# pm-batt-ti.net
KiCad netlist of a schematic drawn in EAGLE
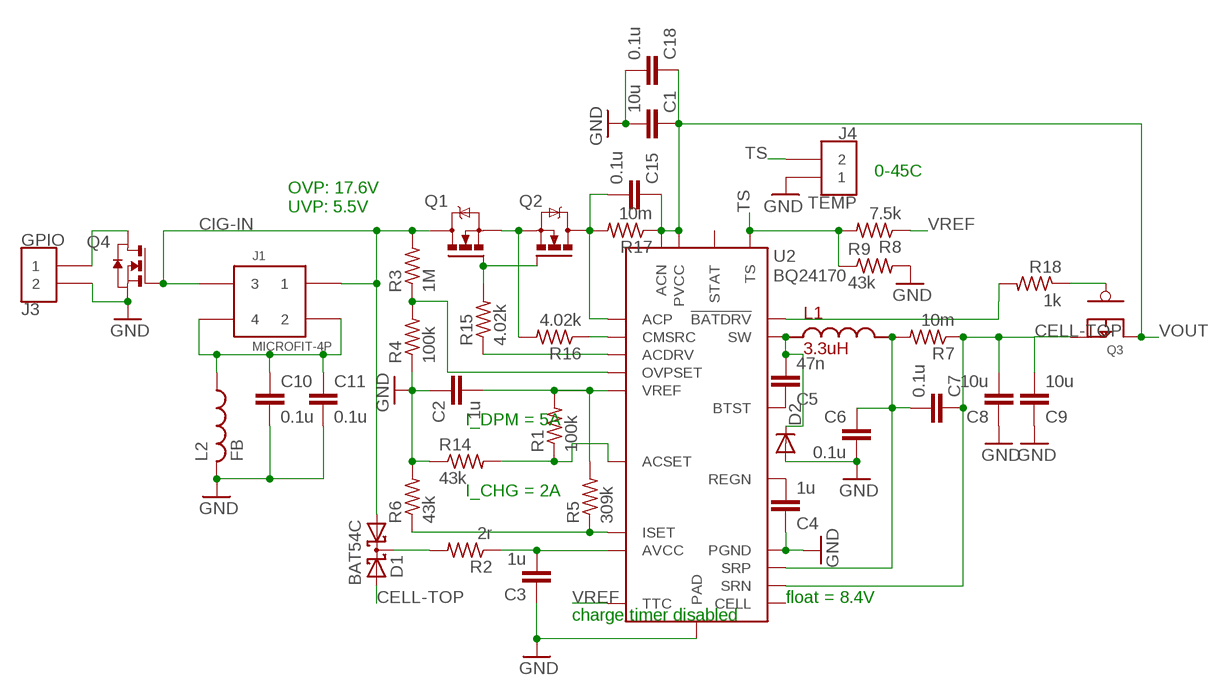
[diagram p0: schematic, sheet 1]
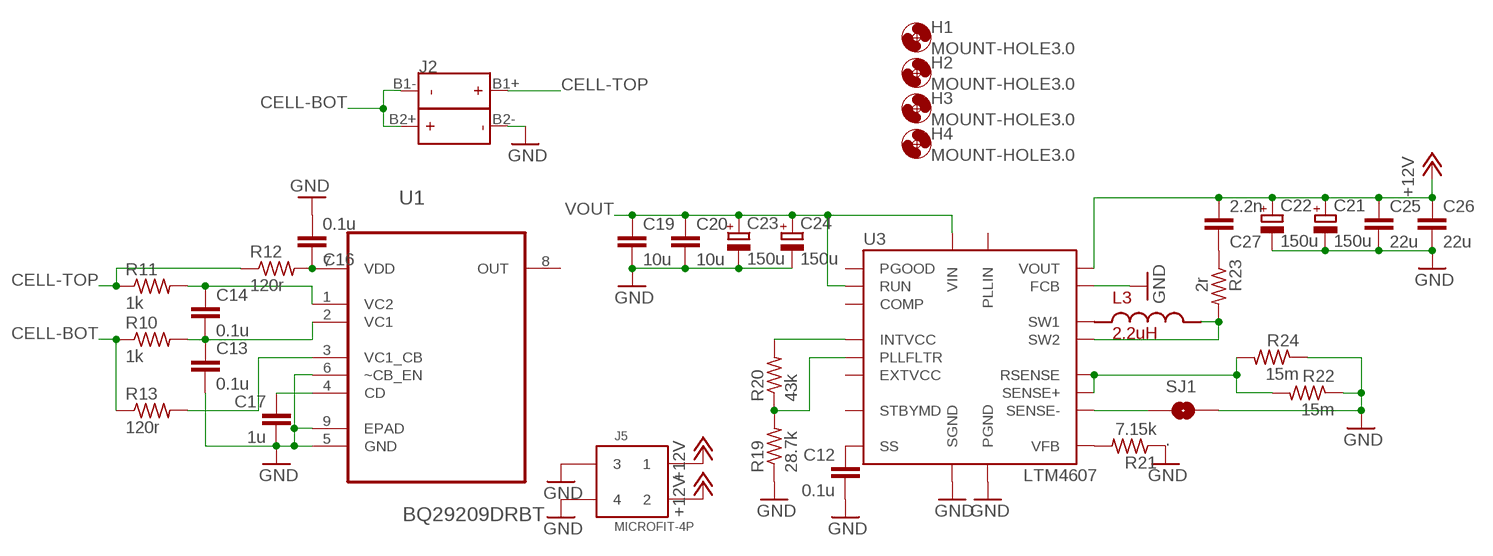
[diagram p1: schematic, sheet 2]

(export (version "E")
  (design (tool "Eeschema 10.0.6"))
  (components
    (comp (ref "C12")
      (value "0.1u")
      (footprint "eagle-import:C0805")
      (libsource (lib "eagle-import") (part "resistor_C-EUC0805"))
    )
    (comp (ref "C13")
      (value "0.1u")
      (footprint "eagle-import:C0603")
      (libsource (lib "eagle-import") (part "C-EUC0603"))
    )
    (comp (ref "C14")
      (value "0.1u")
      (footprint "eagle-import:C0603")
      (libsource (lib "eagle-import") (part "C-EUC0603"))
    )
    (comp (ref "C16")
      (value "0.1u")
      (footprint "eagle-import:C0603")
      (libsource (lib "eagle-import") (part "C-EUC0603"))
    )
    (comp (ref "C17")
      (value "1u")
      (footprint "eagle-import:C0603")
      (libsource (lib "eagle-import") (part "C-EUC0603"))
    )
    (comp (ref "C19")
      (value "10u")
      (footprint "eagle-import:C1206")
      (libsource (lib "eagle-import") (part "C-EUC1206"))
    )
    (comp (ref "C20")
      (value "10u")
      (footprint "eagle-import:C1206")
      (libsource (lib "eagle-import") (part "C-EUC1206"))
    )
    (comp (ref "C21")
      (value "150u")
      (footprint "eagle-import:C2917")
      (libsource (lib "eagle-import") (part "CAP2917"))
    )
    (comp (ref "C22")
      (value "150u")
      (footprint "eagle-import:C2917")
      (libsource (lib "eagle-import") (part "CAP2917"))
    )
    (comp (ref "C23")
      (value "150u")
      (footprint "eagle-import:C2917")
      (libsource (lib "eagle-import") (part "CAP2917"))
    )
    (comp (ref "C24")
      (value "150u")
      (footprint "eagle-import:C2917")
      (libsource (lib "eagle-import") (part "CAP2917"))
    )
    (comp (ref "C25")
      (value "22u")
      (footprint "eagle-import:C1206")
      (libsource (lib "eagle-import") (part "C-EUC1206"))
    )
    (comp (ref "C26")
      (value "22u")
      (footprint "eagle-import:C1206")
      (libsource (lib "eagle-import") (part "C-EUC1206"))
    )
    (comp (ref "C27")
      (value "2.2n")
      (footprint "eagle-import:C0603")
      (libsource (lib "eagle-import") (part "C-EUC0603"))
    )
    (comp (ref "H1")
      (value "MOUNT-HOLE3.0")
      (footprint "eagle-import:3,0")
      (libsource (lib "eagle-import") (part "MOUNT-HOLE3.0"))
    )
    (comp (ref "H2")
      (value "MOUNT-HOLE3.0")
      (footprint "eagle-import:3,0")
      (libsource (lib "eagle-import") (part "MOUNT-HOLE3.0"))
    )
    (comp (ref "H3")
      (value "MOUNT-HOLE3.0")
      (footprint "eagle-import:3,0")
      (libsource (lib "eagle-import") (part "MOUNT-HOLE3.0"))
    )
    (comp (ref "H4")
      (value "MOUNT-HOLE3.0")
      (footprint "eagle-import:3,0")
      (libsource (lib "eagle-import") (part "MOUNT-HOLE3.0"))
    )
    (comp (ref "J2")
      (value "18650X2")
      (footprint "eagle-import:K1048")
      (libsource (lib "eagle-import") (part "18650X2"))
    )
    (comp (ref "J5")
      (value "MICROFIT-4P")
      (footprint "eagle-import:MICROFIT-4P")
      (libsource (lib "eagle-import") (part "MICROFIT-4P"))
    )
    (comp (ref "L3")
      (value "2.2uH")
      (footprint "eagle-import:L-VISHAY-IHLP2020CZ01")
      (libsource (lib "eagle-import") (part "INDUCTORSVISHAY"))
    )
    (comp (ref "R10")
      (value "1k")
      (footprint "eagle-import:R0603")
      (libsource (lib "eagle-import") (part "resistor_R-US_R0603"))
    )
    (comp (ref "R11")
      (value "1k")
      (footprint "eagle-import:R0603")
      (libsource (lib "eagle-import") (part "resistor_R-US_R0603"))
    )
    (comp (ref "R12")
      (value "120r")
      (footprint "eagle-import:R0603")
      (libsource (lib "eagle-import") (part "resistor_R-US_R0603"))
    )
    (comp (ref "R13")
      (value "120r")
      (footprint "eagle-import:R0603")
      (libsource (lib "eagle-import") (part "resistor_R-US_R0603"))
    )
    (comp (ref "R19")
      (value "28.7k")
      (footprint "eagle-import:R0603")
      (libsource (lib "eagle-import") (part "resistor_R-US_R0603"))
    )
    (comp (ref "R20")
      (value "43k")
      (footprint "eagle-import:R0603")
      (libsource (lib "eagle-import") (part "resistor_R-US_R0603"))
    )
    (comp (ref "R21")
      (value "7.15k")
      (footprint "eagle-import:R0603")
      (libsource (lib "eagle-import") (part "resistor_R-US_R0603"))
    )
    (comp (ref "R22")
      (value "15m")
      (footprint "eagle-import:R0805@1")
      (libsource (lib "eagle-import") (part "R-US_R0805"))
    )
    (comp (ref "R23")
      (value "2r")
      (footprint "eagle-import:R0603")
      (libsource (lib "eagle-import") (part "resistor_R-US_R0603"))
    )
    (comp (ref "R24")
      (value "15m")
      (footprint "eagle-import:R0805@1")
      (libsource (lib "eagle-import") (part "R-US_R0805"))
    )
    (comp (ref "SJ1")
      (value ".")
      (footprint "eagle-import:SJ_2S-TRACE")
      (libsource (lib "eagle-import") (part "SOLDERJUMPERTRACE"))
    )
    (comp (ref "U1")
      (value "BQ29209DRBT")
      (footprint "eagle-import:SON65P315X315X100-9N")
      (libsource (lib "eagle-import") (part "BQ29209DRBT"))
    )
    (comp (ref "U3")
      (value "LTM4607")
      (footprint "eagle-import:LTM4607")
      (libsource (lib "eagle-import") (part "LTM4607"))
    )
    (comp (ref "C1")
      (value "10u")
      (footprint "eagle-import:C1206")
      (libsource (lib "eagle-import") (part "C-EUC1206"))
    )
    (comp (ref "C2")
      (value "1u")
      (footprint "eagle-import:C0603")
      (libsource (lib "eagle-import") (part "C-EUC0603"))
    )
    (comp (ref "C3")
      (value "1u")
      (footprint "eagle-import:C0603")
      (libsource (lib "eagle-import") (part "C-EUC0603"))
    )
    (comp (ref "C4")
      (value "1u")
      (footprint "eagle-import:C0603")
      (libsource (lib "eagle-import") (part "C-EUC0603"))
    )
    (comp (ref "C5")
      (value "47n")
      (footprint "eagle-import:C0603")
      (libsource (lib "eagle-import") (part "C-EUC0603"))
    )
    (comp (ref "C6")
      (value "0.1u")
      (footprint "eagle-import:C0603")
      (libsource (lib "eagle-import") (part "C-EUC0603"))
    )
    (comp (ref "C7")
      (value "0.1u")
      (footprint "eagle-import:C0603")
      (libsource (lib "eagle-import") (part "C-EUC0603"))
    )
    (comp (ref "C8")
      (value "10u")
      (footprint "eagle-import:C0805")
      (libsource (lib "eagle-import") (part "C-EUC0805"))
    )
    (comp (ref "C9")
      (value "10u")
      (footprint "eagle-import:C0805")
      (libsource (lib "eagle-import") (part "C-EUC0805"))
    )
    (comp (ref "C10")
      (value "0.1u")
      (footprint "eagle-import:C0603")
      (libsource (lib "eagle-import") (part "C-EUC0603"))
    )
    (comp (ref "C11")
      (value "0.1u")
      (footprint "eagle-import:C0603")
      (libsource (lib "eagle-import") (part "C-EUC0603"))
    )
    (comp (ref "C15")
      (value "0.1u")
      (footprint "eagle-import:C0603")
      (libsource (lib "eagle-import") (part "C-EUC0603"))
    )
    (comp (ref "C18")
      (value "0.1u")
      (footprint "eagle-import:C0603")
      (libsource (lib "eagle-import") (part "C-EUC0603"))
    )
    (comp (ref "D1")
      (value "BAT54C")
      (footprint "eagle-import:SOT23")
      (libsource (lib "eagle-import") (part "BAT54C"))
    )
    (comp (ref "D2")
      (value "DIODESMA-ALT")
      (footprint "eagle-import:SMA-DIODE_ALT")
      (libsource (lib "eagle-import") (part "DIODESMA-ALT"))
    )
    (comp (ref "J1")
      (value "MICROFIT-4P")
      (footprint "eagle-import:MICROFIT-4P")
      (libsource (lib "eagle-import") (part "MICROFIT-4P"))
    )
    (comp (ref "J3")
      (value "GPIO")
      (footprint "eagle-import:MICROFIT-2P")
      (libsource (lib "eagle-import") (part "MICROFIT-2P-RAPTH"))
    )
    (comp (ref "J4")
      (value "TEMP")
      (footprint "eagle-import:MICROFIT-2P")
      (libsource (lib "eagle-import") (part "MICROFIT-2P-RAPTH"))
    )
    (comp (ref "L1")
      (value "3.3uH")
      (footprint "eagle-import:L-VISHAY-IHLP2020CZ01")
      (libsource (lib "eagle-import") (part "INDUCTORSVISHAY"))
    )
    (comp (ref "L2")
      (value "FB")
      (footprint "eagle-import:L3216C")
      (libsource (lib "eagle-import") (part "L-USL3216C"))
    )
    (comp (ref "Q1")
      (value "FDB047N10")
      (footprint "eagle-import:D2_PAK")
      (libsource (lib "eagle-import") (part "FDB047N10"))
    )
    (comp (ref "Q2")
      (value "FDB047N10")
      (footprint "eagle-import:D2_PAK")
      (libsource (lib "eagle-import") (part "FDB047N10"))
    )
    (comp (ref "Q3")
      (value "SUM110P")
      (footprint "eagle-import:D2_PAK")
      (libsource (lib "eagle-import") (part "SUM110P"))
    )
    (comp (ref "Q4")
      (value "NMOSSOT23")
      (footprint "eagle-import:SOT-23")
      (libsource (lib "eagle-import") (part "NMOSSOT23"))
    )
    (comp (ref "R1")
      (value "100k")
      (footprint "eagle-import:R0603")
      (libsource (lib "eagle-import") (part "resistor_R-US_R0603"))
    )
    (comp (ref "R2")
      (value "2r")
      (footprint "eagle-import:R0603")
      (libsource (lib "eagle-import") (part "resistor_R-US_R0603"))
    )
    (comp (ref "R3")
      (value "1M")
      (footprint "eagle-import:R0603")
      (libsource (lib "eagle-import") (part "resistor_R-US_R0603"))
    )
    (comp (ref "R4")
      (value "100k")
      (footprint "eagle-import:R0603")
      (libsource (lib "eagle-import") (part "resistor_R-US_R0603"))
    )
    (comp (ref "R5")
      (value "309k")
      (footprint "eagle-import:R0603")
      (libsource (lib "eagle-import") (part "resistor_R-US_R0603"))
    )
    (comp (ref "R6")
      (value "43k")
      (footprint "eagle-import:R0603")
      (libsource (lib "eagle-import") (part "resistor_R-US_R0603"))
    )
    (comp (ref "R7")
      (value "10m")
      (footprint "eagle-import:R0805")
      (libsource (lib "eagle-import") (part "resistor_R-US_R0805"))
    )
    (comp (ref "R8")
      (value "7.5k")
      (footprint "eagle-import:R0603")
      (libsource (lib "eagle-import") (part "resistor_R-US_R0603"))
    )
    (comp (ref "R9")
      (value "43k")
      (footprint "eagle-import:R0603")
      (libsource (lib "eagle-import") (part "resistor_R-US_R0603"))
    )
    (comp (ref "R14")
      (value "43k")
      (footprint "eagle-import:R0603")
      (libsource (lib "eagle-import") (part "resistor_R-US_R0603"))
    )
    (comp (ref "R15")
      (value "4.02k")
      (footprint "eagle-import:R0603")
      (libsource (lib "eagle-import") (part "resistor_R-US_R0603"))
    )
    (comp (ref "R16")
      (value "4.02k")
      (footprint "eagle-import:R0603")
      (libsource (lib "eagle-import") (part "resistor_R-US_R0603"))
    )
    (comp (ref "R17")
      (value "10m")
      (footprint "eagle-import:R0805")
      (libsource (lib "eagle-import") (part "resistor_R-US_R0805"))
    )
    (comp (ref "R18")
      (value "1k")
      (footprint "eagle-import:R0603")
      (libsource (lib "eagle-import") (part "resistor_R-US_R0603"))
    )
    (comp (ref "U2")
      (value "BQ24170")
      (footprint "eagle-import:QFN-24-TP")
      (libsource (lib "eagle-import") (part "BQ24170"))
    )
  )
  (nets
    (net (code "1") (name "+12V") (class "Default")
      (node (ref "C21") (pin "+") (pinfunction "+_+") (pintype "passive"))
      (node (ref "C22") (pin "+") (pinfunction "+_+") (pintype "passive"))
      (node (ref "C25") (pin "1") (pinfunction "1_1") (pintype "passive"))
      (node (ref "C26") (pin "1") (pinfunction "1_1") (pintype "passive"))
      (node (ref "C27") (pin "2") (pinfunction "2_2") (pintype "passive"))
      (node (ref "J5") (pin "1") (pinfunction "1_1") (pintype "bidirectional"))
      (node (ref "J5") (pin "2") (pinfunction "2_2") (pintype "bidirectional"))
      (node (ref "U3") (pin "E1") (pinfunction "VOUT_E1") (pintype "bidirectional"))
      (node (ref "U3") (pin "E2") (pinfunction "VOUT_E2") (pintype "bidirectional"))
      (node (ref "U3") (pin "F1") (pinfunction "VOUT_F1") (pintype "bidirectional"))
      (node (ref "U3") (pin "F2") (pinfunction "VOUT_F2") (pintype "bidirectional"))
      (node (ref "U3") (pin "F3") (pinfunction "VOUT_F3") (pintype "bidirectional"))
      (node (ref "U3") (pin "F4") (pinfunction "VOUT_F4") (pintype "bidirectional"))
      (node (ref "U3") (pin "G1") (pinfunction "VOUT_G1") (pintype "bidirectional"))
      (node (ref "U3") (pin "G2") (pinfunction "VOUT_G2") (pintype "bidirectional"))
      (node (ref "U3") (pin "G3") (pinfunction "VOUT_G3") (pintype "bidirectional"))
      (node (ref "U3") (pin "G4") (pinfunction "VOUT_G4") (pintype "bidirectional"))
      (node (ref "U3") (pin "H1") (pinfunction "VOUT_H1") (pintype "bidirectional"))
      (node (ref "U3") (pin "H2") (pinfunction "VOUT_H2") (pintype "bidirectional"))
      (node (ref "U3") (pin "H3") (pinfunction "VOUT_H3") (pintype "bidirectional"))
      (node (ref "U3") (pin "H4") (pinfunction "VOUT_H4") (pintype "bidirectional"))
    )
    (net (code "2") (name "CELL-BOT") (class "Default")
      (node (ref "J2") (pin "B1-") (pinfunction "P$2_B1-") (pintype "bidirectional"))
      (node (ref "J2") (pin "B2+") (pinfunction "P$3_B2+") (pintype "bidirectional"))
      (node (ref "R10") (pin "1") (pinfunction "1_1") (pintype "passive"))
      (node (ref "R13") (pin "1") (pinfunction "1_1") (pintype "passive"))
    )
    (net (code "3") (name "CELL-TOP") (class "Default")
      (node (ref "C7") (pin "1") (pinfunction "1_1") (pintype "passive"))
      (node (ref "C8") (pin "2") (pinfunction "2_2") (pintype "passive"))
      (node (ref "C9") (pin "2") (pinfunction "2_2") (pintype "passive"))
      (node (ref "D1") (pin "2") (pinfunction "A2_2") (pintype "passive"))
      (node (ref "J2") (pin "B1+") (pinfunction "P$1_B1+") (pintype "bidirectional"))
      (node (ref "Q3") (pin "3") (pinfunction "S3_3") (pintype "bidirectional"))
      (node (ref "R11") (pin "1") (pinfunction "1_1") (pintype "passive"))
      (node (ref "R12") (pin "1") (pinfunction "1_1") (pintype "passive"))
      (node (ref "R7") (pin "1") (pinfunction "1_1") (pintype "passive"))
      (node (ref "U2") (pin "15") (pinfunction "SRN_15") (pintype "bidirectional"))
    )
    (net (code "4") (name "CIG-IN") (class "Default")
      (node (ref "D1") (pin "1") (pinfunction "A1_1") (pintype "passive"))
      (node (ref "J1") (pin "1") (pinfunction "1_1") (pintype "bidirectional"))
      (node (ref "J1") (pin "3") (pinfunction "3_3") (pintype "bidirectional"))
      (node (ref "Q1") (pin "4") (pinfunction "D_4") (pintype "passive"))
      (node (ref "Q4") (pin "3") (pinfunction "G_3") (pintype "passive"))
      (node (ref "R3") (pin "2") (pinfunction "2_2") (pintype "passive"))
    )
    (net (code "5") (name "GND") (class "Default")
      (node (ref "C1") (pin "2") (pinfunction "2_2") (pintype "passive"))
      (node (ref "C10") (pin "2") (pinfunction "2_2") (pintype "passive"))
      (node (ref "C11") (pin "2") (pinfunction "2_2") (pintype "passive"))
      (node (ref "C12") (pin "2") (pinfunction "2_2") (pintype "passive"))
      (node (ref "C13") (pin "2") (pinfunction "2_2") (pintype "passive"))
      (node (ref "C16") (pin "2") (pinfunction "2_2") (pintype "passive"))
      (node (ref "C17") (pin "2") (pinfunction "2_2") (pintype "passive"))
      (node (ref "C18") (pin "2") (pinfunction "2_2") (pintype "passive"))
      (node (ref "C19") (pin "2") (pinfunction "2_2") (pintype "passive"))
      (node (ref "C2") (pin "1") (pinfunction "1_1") (pintype "passive"))
      (node (ref "C20") (pin "2") (pinfunction "2_2") (pintype "passive"))
      (node (ref "C21") (pin "-") (pinfunction "-_-") (pintype "passive"))
      (node (ref "C22") (pin "-") (pinfunction "-_-") (pintype "passive"))
      (node (ref "C23") (pin "-") (pinfunction "-_-") (pintype "passive"))
      (node (ref "C24") (pin "-") (pinfunction "-_-") (pintype "passive"))
      (node (ref "C25") (pin "2") (pinfunction "2_2") (pintype "passive"))
      (node (ref "C26") (pin "2") (pinfunction "2_2") (pintype "passive"))
      (node (ref "C3") (pin "1") (pinfunction "1_1") (pintype "passive"))
      (node (ref "C4") (pin "1") (pinfunction "1_1") (pintype "passive"))
      (node (ref "C6") (pin "2") (pinfunction "2_2") (pintype "passive"))
      (node (ref "C8") (pin "1") (pinfunction "1_1") (pintype "passive"))
      (node (ref "C9") (pin "1") (pinfunction "1_1") (pintype "passive"))
      (node (ref "D2") (pin "A") (pinfunction "A_A") (pintype "passive"))
      (node (ref "J2") (pin "B2-") (pinfunction "P$4_B2-") (pintype "bidirectional"))
      (node (ref "J3") (pin "P$2") (pinfunction "2_P$2") (pintype "bidirectional"))
      (node (ref "J4") (pin "P$1") (pinfunction "1_P$1") (pintype "bidirectional"))
      (node (ref "J5") (pin "3") (pinfunction "3_3") (pintype "bidirectional"))
      (node (ref "J5") (pin "4") (pinfunction "4_4") (pintype "bidirectional"))
      (node (ref "L2") (pin "2") (pinfunction "2_2") (pintype "passive"))
      (node (ref "Q4") (pin "2") (pinfunction "S_2") (pintype "passive"))
      (node (ref "R14") (pin "1") (pinfunction "1_1") (pintype "passive"))
      (node (ref "R19") (pin "1") (pinfunction "1_1") (pintype "passive"))
      (node (ref "R21") (pin "1") (pinfunction "1_1") (pintype "passive"))
      (node (ref "R22") (pin "1") (pinfunction "1_1") (pintype "passive"))
      (node (ref "R24") (pin "1") (pinfunction "1_1") (pintype "passive"))
      (node (ref "R4") (pin "1") (pinfunction "1_1") (pintype "passive"))
      (node (ref "R6") (pin "2") (pinfunction "2_2") (pintype "passive"))
      (node (ref "R9") (pin "2") (pinfunction "2_2") (pintype "passive"))
      (node (ref "SJ1") (pin "2") (pinfunction "2_2") (pintype "passive"))
      (node (ref "U1") (pin "5") (pinfunction "GND_5") (pintype "passive"))
      (node (ref "U1") (pin "6") (pinfunction "~{CB_EN}_6") (pintype "input"))
      (node (ref "U1") (pin "9") (pinfunction "EPAD_9") (pintype "passive"))
      (node (ref "U2") (pin "22") (pinfunction "PGND_22") (pintype "bidirectional"))
      (node (ref "U2") (pin "23") (pinfunction "PGND_23") (pintype "bidirectional"))
      (node (ref "U2") (pin "TP") (pinfunction "PAD_TP") (pintype "bidirectional"))
      (node (ref "U3") (pin "A1") (pinfunction "PGND_A1") (pintype "bidirectional"))
      (node (ref "U3") (pin "A11") (pinfunction "PGND_A11") (pintype "bidirectional"))
      (node (ref "U3") (pin "A12") (pinfunction "PGND_A12") (pintype "bidirectional"))
      (node (ref "U3") (pin "A2") (pinfunction "PGND_A2") (pintype "bidirectional"))
      (node (ref "U3") (pin "A3") (pinfunction "PGND_A3") (pintype "bidirectional"))
      (node (ref "U3") (pin "A7") (pinfunction "SGND_A7") (pintype "bidirectional"))
      (node (ref "U3") (pin "A9") (pinfunction "FCB_A9") (pintype "bidirectional"))
      (node (ref "U3") (pin "B1") (pinfunction "PGND_B1") (pintype "bidirectional"))
      (node (ref "U3") (pin "B10") (pinfunction "PGND_B10") (pintype "bidirectional"))
      (node (ref "U3") (pin "B11") (pinfunction "PGND_B11") (pintype "bidirectional"))
      (node (ref "U3") (pin "B12") (pinfunction "PGND_B12") (pintype "bidirectional"))
      (node (ref "U3") (pin "B2") (pinfunction "PGND_B2") (pintype "bidirectional"))
      (node (ref "U3") (pin "B3") (pinfunction "PGND_B3") (pintype "bidirectional"))
      (node (ref "U3") (pin "B4") (pinfunction "PGND_B4") (pintype "bidirectional"))
      (node (ref "U3") (pin "C1") (pinfunction "PGND_C1") (pintype "bidirectional"))
      (node (ref "U3") (pin "C10") (pinfunction "PGND_C10") (pintype "bidirectional"))
      (node (ref "U3") (pin "C11") (pinfunction "PGND_C11") (pintype "bidirectional"))
      (node (ref "U3") (pin "C12") (pinfunction "PGND_C12") (pintype "bidirectional"))
      (node (ref "U3") (pin "C2") (pinfunction "PGND_C2") (pintype "bidirectional"))
      (node (ref "U3") (pin "C3") (pinfunction "PGND_C3") (pintype "bidirectional"))
      (node (ref "U3") (pin "C4") (pinfunction "PGND_C4") (pintype "bidirectional"))
      (node (ref "U3") (pin "C5") (pinfunction "PGND_C5") (pintype "bidirectional"))
      (node (ref "U3") (pin "C6") (pinfunction "PGND_C6") (pintype "bidirectional"))
      (node (ref "U3") (pin "C7") (pinfunction "PGND_C7") (pintype "bidirectional"))
      (node (ref "U3") (pin "C8") (pinfunction "PGND_C8") (pintype "bidirectional"))
      (node (ref "U3") (pin "C9") (pinfunction "PGND_C9") (pintype "bidirectional"))
      (node (ref "U3") (pin "D1") (pinfunction "PGND_D1") (pintype "bidirectional"))
      (node (ref "U3") (pin "D10") (pinfunction "PGND_D10") (pintype "bidirectional"))
      (node (ref "U3") (pin "D11") (pinfunction "PGND_D11") (pintype "bidirectional"))
      (node (ref "U3") (pin "D12") (pinfunction "PGND_D12") (pintype "bidirectional"))
      (node (ref "U3") (pin "D2") (pinfunction "PGND_D2") (pintype "bidirectional"))
      (node (ref "U3") (pin "D3") (pinfunction "PGND_D3") (pintype "bidirectional"))
      (node (ref "U3") (pin "D4") (pinfunction "PGND_D4") (pintype "bidirectional"))
      (node (ref "U3") (pin "D5") (pinfunction "PGND_D5") (pintype "bidirectional"))
      (node (ref "U3") (pin "D6") (pinfunction "PGND_D6") (pintype "bidirectional"))
      (node (ref "U3") (pin "D7") (pinfunction "PGND_D7") (pintype "bidirectional"))
      (node (ref "U3") (pin "D8") (pinfunction "PGND_D8") (pintype "bidirectional"))
      (node (ref "U3") (pin "D9") (pinfunction "PGND_D9") (pintype "bidirectional"))
      (node (ref "U3") (pin "E10") (pinfunction "PGND_E10") (pintype "bidirectional"))
      (node (ref "U3") (pin "E11") (pinfunction "PGND_E11") (pintype "bidirectional"))
      (node (ref "U3") (pin "E12") (pinfunction "PGND_E12") (pintype "bidirectional"))
      (node (ref "U3") (pin "E3") (pinfunction "PGND_E3") (pintype "bidirectional"))
      (node (ref "U3") (pin "E4") (pinfunction "PGND_E4") (pintype "bidirectional"))
      (node (ref "U3") (pin "E5") (pinfunction "PGND_E5") (pintype "bidirectional"))
      (node (ref "U3") (pin "E6") (pinfunction "PGND_E6") (pintype "bidirectional"))
      (node (ref "U3") (pin "E7") (pinfunction "PGND_E7") (pintype "bidirectional"))
      (node (ref "U3") (pin "E8") (pinfunction "PGND_E8") (pintype "bidirectional"))
      (node (ref "U3") (pin "E9") (pinfunction "PGND_E9") (pintype "bidirectional"))
    )
    (net (code "6") (name "Net-(C5-Pad2)") (class "Default")
      (node (ref "C5") (pin "2") (pinfunction "2_2") (pintype "passive"))
      (node (ref "D2") (pin "C") (pinfunction "C_C") (pintype "passive"))
      (node (ref "L1") (pin "P$1") (pinfunction "P$1_P$1") (pintype "bidirectional"))
      (node (ref "U2") (pin "1") (pinfunction "SW_1") (pintype "bidirectional"))
      (node (ref "U2") (pin "24") (pinfunction "SW_24") (pintype "bidirectional"))
    )
    (net (code "7") (name "Net-(C10-Pad1)") (class "Default")
      (node (ref "C10") (pin "1") (pinfunction "1_1") (pintype "passive"))
      (node (ref "C11") (pin "1") (pinfunction "1_1") (pintype "passive"))
      (node (ref "J1") (pin "2") (pinfunction "2_2") (pintype "bidirectional"))
      (node (ref "J1") (pin "4") (pinfunction "4_4") (pintype "bidirectional"))
      (node (ref "L2") (pin "1") (pinfunction "1_1") (pintype "passive"))
    )
    (net (code "8") (name "Net-(C27-Pad1)") (class "Default")
      (node (ref "C27") (pin "1") (pinfunction "1_1") (pintype "passive"))
      (node (ref "R23") (pin "1") (pinfunction "1_1") (pintype "passive"))
    )
    (net (code "9") (name "Net-(D1-CC)") (class "Default")
      (node (ref "D1") (pin "3") (pinfunction "CC_3") (pintype "passive"))
      (node (ref "R2") (pin "2") (pinfunction "2_2") (pintype "passive"))
    )
    (net (code "10") (name "Net-(J3-1)") (class "Default")
      (node (ref "J3") (pin "P$1") (pinfunction "1_P$1") (pintype "bidirectional"))
      (node (ref "Q4") (pin "1") (pinfunction "D_1") (pintype "passive"))
    )
    (net (code "11") (name "Net-(L3-PadP$1)") (class "Default")
      (node (ref "L3") (pin "P$1") (pinfunction "P$1_P$1") (pintype "bidirectional"))
      (node (ref "U3") (pin "J1") (pinfunction "SW1_J1") (pintype "bidirectional"))
      (node (ref "U3") (pin "J2") (pinfunction "SW1_J2") (pintype "bidirectional"))
      (node (ref "U3") (pin "J3") (pinfunction "SW1_J3") (pintype "bidirectional"))
      (node (ref "U3") (pin "J4") (pinfunction "SW1_J4") (pintype "bidirectional"))
      (node (ref "U3") (pin "K1") (pinfunction "SW1_K1") (pintype "bidirectional"))
      (node (ref "U3") (pin "K2") (pinfunction "SW1_K2") (pintype "bidirectional"))
      (node (ref "U3") (pin "K3") (pinfunction "SW1_K3") (pintype "bidirectional"))
      (node (ref "U3") (pin "K4") (pinfunction "SW1_K4") (pintype "bidirectional"))
      (node (ref "U3") (pin "L1") (pinfunction "SW1_L1") (pintype "bidirectional"))
      (node (ref "U3") (pin "L2") (pinfunction "SW1_L2") (pintype "bidirectional"))
      (node (ref "U3") (pin "L3") (pinfunction "SW1_L3") (pintype "bidirectional"))
      (node (ref "U3") (pin "L4") (pinfunction "SW1_L4") (pintype "bidirectional"))
      (node (ref "U3") (pin "M1") (pinfunction "SW1_M1") (pintype "bidirectional"))
      (node (ref "U3") (pin "M2") (pinfunction "SW1_M2") (pintype "bidirectional"))
      (node (ref "U3") (pin "M3") (pinfunction "SW1_M3") (pintype "bidirectional"))
      (node (ref "U3") (pin "M4") (pinfunction "SW1_M4") (pintype "bidirectional"))
    )
    (net (code "12") (name "Net-(L3-PadP$2)") (class "Default")
      (node (ref "L3") (pin "P$2") (pinfunction "P$2_P$2") (pintype "bidirectional"))
      (node (ref "R23") (pin "2") (pinfunction "2_2") (pintype "passive"))
      (node (ref "U3") (pin "J8") (pinfunction "SW2_J8") (pintype "bidirectional"))
      (node (ref "U3") (pin "J9") (pinfunction "SW2_J9") (pintype "bidirectional"))
      (node (ref "U3") (pin "K7") (pinfunction "SW2_K7") (pintype "bidirectional"))
      (node (ref "U3") (pin "K8") (pinfunction "SW2_K8") (pintype "bidirectional"))
      (node (ref "U3") (pin "K9") (pinfunction "SW2_K9") (pintype "bidirectional"))
      (node (ref "U3") (pin "L7") (pinfunction "SW2_L7") (pintype "bidirectional"))
      (node (ref "U3") (pin "L8") (pinfunction "SW2_L8") (pintype "bidirectional"))
      (node (ref "U3") (pin "L9") (pinfunction "SW2_L9") (pintype "bidirectional"))
      (node (ref "U3") (pin "M7") (pinfunction "SW2_M7") (pintype "bidirectional"))
      (node (ref "U3") (pin "M8") (pinfunction "SW2_M8") (pintype "bidirectional"))
      (node (ref "U3") (pin "M9") (pinfunction "SW2_M9") (pintype "bidirectional"))
    )
    (net (code "13") (name "Net-(Q1-G)") (class "Default")
      (node (ref "Q1") (pin "1") (pinfunction "G_1") (pintype "passive"))
      (node (ref "Q2") (pin "1") (pinfunction "G_1") (pintype "passive"))
      (node (ref "R15") (pin "2") (pinfunction "2_2") (pintype "passive"))
    )
    (net (code "14") (name "Net-(Q1-S)") (class "Default")
      (node (ref "Q1") (pin "3") (pinfunction "S_3") (pintype "passive"))
      (node (ref "Q2") (pin "3") (pinfunction "S_3") (pintype "passive"))
      (node (ref "R16") (pin "2") (pinfunction "2_2") (pintype "passive"))
    )
    (net (code "15") (name "Net-(Q2-D)") (class "Default")
      (node (ref "C15") (pin "2") (pinfunction "2_2") (pintype "passive"))
      (node (ref "Q2") (pin "4") (pinfunction "D_4") (pintype "passive"))
      (node (ref "R17") (pin "2") (pinfunction "2_2") (pintype "passive"))
      (node (ref "U2") (pin "6") (pinfunction "ACP_6") (pintype "bidirectional"))
    )
    (net (code "16") (name "Net-(Q3-G4)") (class "Default")
      (node (ref "Q3") (pin "1") (pinfunction "G4_1") (pintype "bidirectional"))
      (node (ref "R18") (pin "1") (pinfunction "1_1") (pintype "passive"))
    )
    (net (code "17") (name "Net-(U1-CD)") (class "Default")
      (node (ref "C17") (pin "1") (pinfunction "1_1") (pintype "passive"))
      (node (ref "U1") (pin "4") (pinfunction "CD_4") (pintype "passive"))
    )
    (net (code "18") (name "Net-(U1-VC1)") (class "Default")
      (node (ref "C13") (pin "1") (pinfunction "1_1") (pintype "passive"))
      (node (ref "C14") (pin "2") (pinfunction "2_2") (pintype "passive"))
      (node (ref "R10") (pin "2") (pinfunction "2_2") (pintype "passive"))
      (node (ref "U1") (pin "2") (pinfunction "VC1_2") (pintype "power_in"))
    )
    (net (code "19") (name "Net-(U1-VC1_CB)") (class "Default")
      (node (ref "R13") (pin "2") (pinfunction "2_2") (pintype "passive"))
      (node (ref "U1") (pin "3") (pinfunction "VC1_CB_3") (pintype "power_in"))
    )
    (net (code "20") (name "Net-(U1-VC2)") (class "Default")
      (node (ref "C14") (pin "1") (pinfunction "1_1") (pintype "passive"))
      (node (ref "R11") (pin "2") (pinfunction "2_2") (pintype "passive"))
      (node (ref "U1") (pin "1") (pinfunction "VC2_1") (pintype "power_in"))
    )
    (net (code "21") (name "Net-(U1-VDD)") (class "Default")
      (node (ref "C16") (pin "1") (pinfunction "1_1") (pintype "passive"))
      (node (ref "R12") (pin "2") (pinfunction "2_2") (pintype "passive"))
      (node (ref "U1") (pin "7") (pinfunction "VDD_7") (pintype "power_in"))
    )
    (net (code "22") (name "Net-(U2-ACDRV)") (class "Default")
      (node (ref "R15") (pin "1") (pinfunction "1_1") (pintype "passive"))
      (node (ref "U2") (pin "8") (pinfunction "ACDRV_8") (pintype "bidirectional"))
    )
    (net (code "23") (name "Net-(U2-ACSET)") (class "Default")
      (node (ref "R1") (pin "1") (pinfunction "1_1") (pintype "passive"))
      (node (ref "R14") (pin "2") (pinfunction "2_2") (pintype "passive"))
      (node (ref "U2") (pin "17") (pinfunction "ACSET_17") (pintype "bidirectional"))
    )
    (net (code "24") (name "Net-(U2-AVCC)") (class "Default")
      (node (ref "C3") (pin "2") (pinfunction "2_2") (pintype "passive"))
      (node (ref "R2") (pin "1") (pinfunction "1_1") (pintype "passive"))
      (node (ref "U2") (pin "4") (pinfunction "AVCC_4") (pintype "bidirectional"))
    )
    (net (code "25") (name "Net-(U2-BTST)") (class "Default")
      (node (ref "C5") (pin "1") (pinfunction "1_1") (pintype "passive"))
      (node (ref "U2") (pin "21") (pinfunction "BTST_21") (pintype "bidirectional"))
    )
    (net (code "26") (name "Net-(U2-CMSRC)") (class "Default")
      (node (ref "R16") (pin "1") (pinfunction "1_1") (pintype "passive"))
      (node (ref "U2") (pin "7") (pinfunction "CMSRC_7") (pintype "bidirectional"))
    )
    (net (code "27") (name "Net-(U2-ISET)") (class "Default")
      (node (ref "R5") (pin "1") (pinfunction "1_1") (pintype "passive"))
      (node (ref "R6") (pin "1") (pinfunction "1_1") (pintype "passive"))
      (node (ref "U2") (pin "13") (pinfunction "ISET_13") (pintype "bidirectional"))
    )
    (net (code "28") (name "Net-(U2-OVPSET)") (class "Default")
      (node (ref "R3") (pin "1") (pinfunction "1_1") (pintype "passive"))
      (node (ref "R4") (pin "2") (pinfunction "2_2") (pintype "passive"))
      (node (ref "U2") (pin "18") (pinfunction "OVPSET_18") (pintype "bidirectional"))
    )
    (net (code "29") (name "Net-(U2-REGN)") (class "Default")
      (node (ref "C4") (pin "2") (pinfunction "2_2") (pintype "passive"))
      (node (ref "U2") (pin "20") (pinfunction "REGN_20") (pintype "bidirectional"))
    )
    (net (code "30") (name "Net-(U2-SRP)") (class "Default")
      (node (ref "C6") (pin "1") (pinfunction "1_1") (pintype "passive"))
      (node (ref "C7") (pin "2") (pinfunction "2_2") (pintype "passive"))
      (node (ref "L1") (pin "P$2") (pinfunction "P$2_P$2") (pintype "bidirectional"))
      (node (ref "R7") (pin "2") (pinfunction "2_2") (pintype "passive"))
      (node (ref "U2") (pin "16") (pinfunction "SRP_16") (pintype "bidirectional"))
    )
    (net (code "31") (name "Net-(U2-~{BATDRV})") (class "Default")
      (node (ref "R18") (pin "2") (pinfunction "2_2") (pintype "passive"))
      (node (ref "U2") (pin "19") (pinfunction "~{BATDRV}_19") (pintype "bidirectional"))
    )
    (net (code "32") (name "Net-(U3-INTVCC)") (class "Default")
      (node (ref "R20") (pin "2") (pinfunction "2_2") (pintype "passive"))
      (node (ref "U3") (pin "F5") (pinfunction "INTVCC_F5") (pintype "bidirectional"))
    )
    (net (code "33") (name "Net-(U3-PLLFLTR)") (class "Default")
      (node (ref "R19") (pin "2") (pinfunction "2_2") (pintype "passive"))
      (node (ref "R20") (pin "1") (pinfunction "1_1") (pintype "passive"))
      (node (ref "U3") (pin "B8") (pinfunction "PLLFLTR_B8") (pintype "bidirectional"))
    )
    (net (code "34") (name "Net-(U3-SENSE+)") (class "Default")
      (node (ref "R22") (pin "2") (pinfunction "2_2") (pintype "passive"))
      (node (ref "R24") (pin "2") (pinfunction "2_2") (pintype "passive"))
      (node (ref "U3") (pin "A4") (pinfunction "SENSE+_A4") (pintype "bidirectional"))
      (node (ref "U3") (pin "F10") (pinfunction "RSENSE_F10") (pintype "bidirectional"))
      (node (ref "U3") (pin "F11") (pinfunction "RSENSE_F11") (pintype "bidirectional"))
      (node (ref "U3") (pin "F12") (pinfunction "RSENSE_F12") (pintype "bidirectional"))
      (node (ref "U3") (pin "G10") (pinfunction "RSENSE_G10") (pintype "bidirectional"))
      (node (ref "U3") (pin "G11") (pinfunction "RSENSE_G11") (pintype "bidirectional"))
      (node (ref "U3") (pin "G12") (pinfunction "RSENSE_G12") (pintype "bidirectional"))
      (node (ref "U3") (pin "G5") (pinfunction "RSENSE_G5") (pintype "bidirectional"))
      (node (ref "U3") (pin "G6") (pinfunction "RSENSE_G6") (pintype "bidirectional"))
      (node (ref "U3") (pin "G7") (pinfunction "RSENSE_G7") (pintype "bidirectional"))
      (node (ref "U3") (pin "G8") (pinfunction "RSENSE_G8") (pintype "bidirectional"))
      (node (ref "U3") (pin "G9") (pinfunction "RSENSE_G9") (pintype "bidirectional"))
      (node (ref "U3") (pin "H10") (pinfunction "RSENSE_H10") (pintype "bidirectional"))
      (node (ref "U3") (pin "H11") (pinfunction "RSENSE_H11") (pintype "bidirectional"))
      (node (ref "U3") (pin "H12") (pinfunction "RSENSE_H12") (pintype "bidirectional"))
      (node (ref "U3") (pin "H5") (pinfunction "RSENSE_H5") (pintype "bidirectional"))
      (node (ref "U3") (pin "H6") (pinfunction "RSENSE_H6") (pintype "bidirectional"))
      (node (ref "U3") (pin "H7") (pinfunction "RSENSE_H7") (pintype "bidirectional"))
      (node (ref "U3") (pin "H8") (pinfunction "RSENSE_H8") (pintype "bidirectional"))
      (node (ref "U3") (pin "H9") (pinfunction "RSENSE_H9") (pintype "bidirectional"))
      (node (ref "U3") (pin "J5") (pinfunction "RSENSE_J5") (pintype "bidirectional"))
      (node (ref "U3") (pin "J6") (pinfunction "RSENSE_J6") (pintype "bidirectional"))
      (node (ref "U3") (pin "J7") (pinfunction "RSENSE_J7") (pintype "bidirectional"))
      (node (ref "U3") (pin "K5") (pinfunction "RSENSE_K5") (pintype "bidirectional"))
      (node (ref "U3") (pin "K6") (pinfunction "RSENSE_K6") (pintype "bidirectional"))
      (node (ref "U3") (pin "L5") (pinfunction "RSENSE_L5") (pintype "bidirectional"))
      (node (ref "U3") (pin "L6") (pinfunction "RSENSE_L6") (pintype "bidirectional"))
      (node (ref "U3") (pin "M5") (pinfunction "RSENSE_M5") (pintype "bidirectional"))
      (node (ref "U3") (pin "M6") (pinfunction "RSENSE_M6") (pintype "bidirectional"))
    )
    (net (code "35") (name "Net-(U3-SENSE-)") (class "Default")
      (node (ref "SJ1") (pin "1") (pinfunction "1_1") (pintype "passive"))
      (node (ref "U3") (pin "A5") (pinfunction "SENSE-_A5") (pintype "bidirectional"))
    )
    (net (code "36") (name "Net-(U3-SS)") (class "Default")
      (node (ref "C12") (pin "1") (pinfunction "1_1") (pintype "passive"))
      (node (ref "U3") (pin "A6") (pinfunction "SS_A6") (pintype "bidirectional"))
    )
    (net (code "37") (name "Net-(U3-VFB)") (class "Default")
      (node (ref "R21") (pin "2") (pinfunction "2_2") (pintype "passive"))
      (node (ref "U3") (pin "B6") (pinfunction "VFB_B6") (pintype "bidirectional"))
    )
    (net (code "38") (name "TS") (class "Default")
      (node (ref "J4") (pin "P$2") (pinfunction "2_P$2") (pintype "bidirectional"))
      (node (ref "R8") (pin "2") (pinfunction "2_2") (pintype "passive"))
      (node (ref "R9") (pin "1") (pinfunction "1_1") (pintype "passive"))
      (node (ref "U2") (pin "10") (pinfunction "TS_10") (pintype "bidirectional"))
    )
    (net (code "39") (name "VOUT") (class "Default")
      (node (ref "C1") (pin "1") (pinfunction "1_1") (pintype "passive"))
      (node (ref "C15") (pin "1") (pinfunction "1_1") (pintype "passive"))
      (node (ref "C18") (pin "1") (pinfunction "1_1") (pintype "passive"))
      (node (ref "C19") (pin "1") (pinfunction "1_1") (pintype "passive"))
      (node (ref "C20") (pin "1") (pinfunction "1_1") (pintype "passive"))
      (node (ref "C23") (pin "+") (pinfunction "+_+") (pintype "passive"))
      (node (ref "C24") (pin "+") (pinfunction "+_+") (pintype "passive"))
      (node (ref "Q3") (pin "4") (pinfunction "D8_4") (pintype "bidirectional"))
      (node (ref "R17") (pin "1") (pinfunction "1_1") (pintype "passive"))
      (node (ref "U2") (pin "2") (pinfunction "PVCC_2") (pintype "bidirectional"))
      (node (ref "U2") (pin "3") (pinfunction "PVCC_3") (pintype "bidirectional"))
      (node (ref "U2") (pin "5") (pinfunction "ACN_5") (pintype "bidirectional"))
      (node (ref "U3") (pin "A8") (pinfunction "RUN_A8") (pintype "bidirectional"))
      (node (ref "U3") (pin "J10") (pinfunction "VIN_J10") (pintype "bidirectional"))
      (node (ref "U3") (pin "J11") (pinfunction "VIN_J11") (pintype "bidirectional"))
      (node (ref "U3") (pin "J12") (pinfunction "VIN_J12") (pintype "bidirectional"))
      (node (ref "U3") (pin "K10") (pinfunction "VIN_K10") (pintype "bidirectional"))
      (node (ref "U3") (pin "K11") (pinfunction "VIN_K11") (pintype "bidirectional"))
      (node (ref "U3") (pin "K12") (pinfunction "VIN_K12") (pintype "bidirectional"))
      (node (ref "U3") (pin "L10") (pinfunction "VIN_L10") (pintype "bidirectional"))
      (node (ref "U3") (pin "L11") (pinfunction "VIN_L11") (pintype "bidirectional"))
      (node (ref "U3") (pin "L12") (pinfunction "VIN_L12") (pintype "bidirectional"))
      (node (ref "U3") (pin "M10") (pinfunction "VIN_M10") (pintype "bidirectional"))
      (node (ref "U3") (pin "M11") (pinfunction "VIN_M11") (pintype "bidirectional"))
      (node (ref "U3") (pin "M12") (pinfunction "VIN_M12") (pintype "bidirectional"))
    )
    (net (code "40") (name "VREF") (class "Default")
      (node (ref "C2") (pin "2") (pinfunction "2_2") (pintype "passive"))
      (node (ref "R1") (pin "2") (pinfunction "2_2") (pintype "passive"))
      (node (ref "R5") (pin "2") (pinfunction "2_2") (pintype "passive"))
      (node (ref "R8") (pin "1") (pinfunction "1_1") (pintype "passive"))
      (node (ref "U2") (pin "11") (pinfunction "TTC_11") (pintype "bidirectional"))
      (node (ref "U2") (pin "12") (pinfunction "VREF_12") (pintype "bidirectional"))
    )
    (net (code "41") (name "unconnected-(U1-OUT-Pad8)") (class "Default")
      (node (ref "U1") (pin "8") (pinfunction "OUT_8") (pintype "output"))
    )
    (net (code "42") (name "unconnected-(U2-CELL-Pad14)") (class "Default")
      (node (ref "U2") (pin "14") (pinfunction "CELL_14") (pintype "bidirectional"))
    )
    (net (code "43") (name "unconnected-(U2-STAT-Pad9)") (class "Default")
      (node (ref "U2") (pin "9") (pinfunction "STAT_9") (pintype "bidirectional"))
    )
    (net (code "44") (name "unconnected-(U3-COMP-PadB7)") (class "Default")
      (node (ref "U3") (pin "B7") (pinfunction "COMP_B7") (pintype "bidirectional"))
    )
    (net (code "45") (name "unconnected-(U3-EXTVCC-PadF6)") (class "Default")
      (node (ref "U3") (pin "F6") (pinfunction "EXTVCC_F6") (pintype "bidirectional"))
    )
    (net (code "46") (name "unconnected-(U3-PGOOD-PadB5)") (class "Default")
      (node (ref "U3") (pin "B5") (pinfunction "PGOOD_B5") (pintype "bidirectional"))
    )
    (net (code "47") (name "unconnected-(U3-PLLIN-PadB9)") (class "Default")
      (node (ref "U3") (pin "B9") (pinfunction "PLLIN_B9") (pintype "bidirectional"))
    )
    (net (code "48") (name "unconnected-(U3-STBYMD-PadA10)") (class "Default")
      (node (ref "U3") (pin "A10") (pinfunction "STBYMD_A10") (pintype "bidirectional"))
    )
  )
)
